# Sheet.net
KiCad netlist of a schematic drawn in Altium Designer
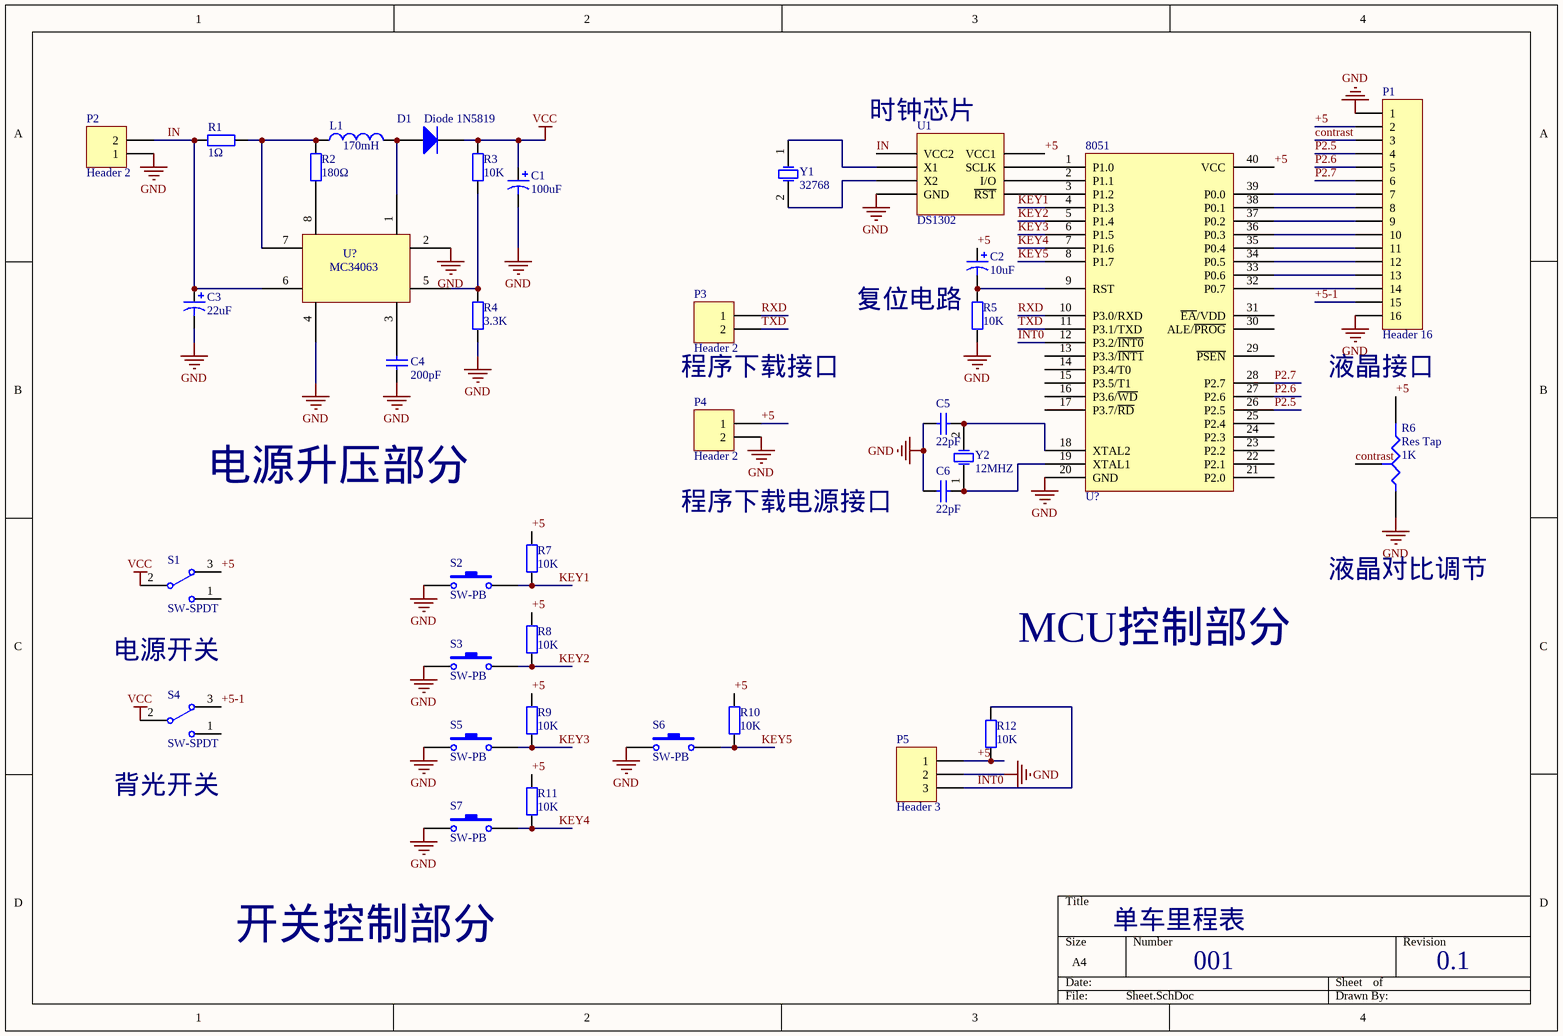
[diagram p0: Sheet.SchDoc]

(export (version "E")
  (design (tool "Eeschema 10.0.6"))
  (components
    (comp (ref "8051") (value "U?") (footprint "DIP-40") (libsource (lib "Schlib") (part "8051")))
    (comp (ref "C1")
      (value "100uF")
      (footprint "CAP-.1/.3")
      (description "Polarized Capacitor (Radial)")
      (fields (field (name "Comment") "Cap Pol1") (field (name "PUBLISHER") "Altium Limited"))
      (libsource (lib "Miscellaneous Devices") (part "Cap Pol1"))
    )
    (comp (ref "C2")
      (value "10uF")
      (footprint "CAP-.1/.2")
      (description "Polarized Capacitor (Radial)")
      (fields (field (name "Comment") "Cap Pol1") (field (name "PUBLISHER") "Altium Limited"))
      (libsource (lib "Miscellaneous Devices") (part "Cap Pol1"))
    )
    (comp (ref "C3")
      (value "22uF")
      (footprint "CAP-.1/.2")
      (description "Polarized Capacitor (Radial)")
      (fields (field (name "Comment") "Cap Pol1") (field (name "PUBLISHER") "Altium Limited"))
      (libsource (lib "Miscellaneous Devices") (part "Cap Pol1"))
    )
    (comp (ref "C4")
      (value "200pF")
      (footprint "CAP")
      (description "Capacitor")
      (fields (field (name "Comment") "Cap") (field (name "PUBLISHER") "Altium Limited"))
      (libsource (lib "Miscellaneous Devices") (part "Cap"))
    )
    (comp (ref "C5")
      (value "22pF")
      (footprint "CAP")
      (description "Capacitor")
      (fields (field (name "Comment") "Cap") (field (name "PUBLISHER") "Altium Limited"))
      (libsource (lib "Miscellaneous Devices") (part "Cap"))
    )
    (comp (ref "C6")
      (value "22pF")
      (footprint "CAP")
      (description "Capacitor")
      (fields (field (name "Comment") "Cap") (field (name "PUBLISHER") "Altium Limited"))
      (libsource (lib "Miscellaneous Devices") (part "Cap"))
    )
    (comp (ref "D1")
      (value "Diode 1N5819")
      (footprint "DO-41")
      (description "1 Amp General Purpose Rectifier")
      (fields (field (name "PUBLISHER") "Altium Limited"))
      (libsource (lib "Miscellaneous Devices") (part "Diode 1N4001"))
    )
    (comp (ref "L1")
      (value "170mH")
      (footprint "Inductor")
      (description "Inductor")
      (fields (field (name "PUBLISHER") "Altium Limited"))
      (libsource (lib "Miscellaneous Devices") (part "Inductor"))
    )
    (comp (ref "MC34063") (value "U?") (footprint "DIP-8") (libsource (lib "Schlib") (part "MC34063")))
    (comp (ref "P1")
      (value "Header 16")
      (footprint "HDR1X16")
      (description "Header, 16-Pin")
      (fields (field (name "PUBLISHER") "Altium Limited"))
      (libsource (lib "Miscellaneous Connectors") (part "Header 16"))
    )
    (comp (ref "P2")
      (value "Header 2")
      (footprint "HDR1X2")
      (description "Header, 2-Pin")
      (fields (field (name "PUBLISHER") "Altium Limited"))
      (libsource (lib "") (part "Header 2_1"))
    )
    (comp (ref "P3")
      (value "Header 2")
      (footprint "HDR1X2")
      (description "Header, 2-Pin")
      (fields (field (name "PUBLISHER") "Altium Limited"))
      (libsource (lib "Miscellaneous Connectors") (part "Header 2"))
    )
    (comp (ref "P4")
      (value "Header 2")
      (footprint "HDR1X2")
      (description "Header, 2-Pin")
      (fields (field (name "PUBLISHER") "Altium Limited"))
      (libsource (lib "Miscellaneous Connectors") (part "Header 2"))
    )
    (comp (ref "P5")
      (value "Header 3")
      (footprint "HDR1X3")
      (description "Header, 3-Pin")
      (fields (field (name "PUBLISHER") "Altium Limited"))
      (libsource (lib "Miscellaneous Connectors") (part "Header 3"))
    )
    (comp (ref "R1")
      (value "1Ω")
      (footprint "AXIAL-0.4")
      (description "Resistor")
      (fields (field (name "Comment") "Res2") (field (name "PUBLISHER") "Altium Limited"))
      (libsource (lib "") (part "Res2_1"))
    )
    (comp (ref "R2")
      (value "180Ω")
      (footprint "AXIAL-0.4")
      (description "Resistor")
      (fields (field (name "Comment") "Res2") (field (name "PUBLISHER") "Altium Limited"))
      (libsource (lib "") (part "Res2_2"))
    )
    (comp (ref "R3")
      (value "10K")
      (footprint "AXIAL-0.4")
      (description "Resistor")
      (fields (field (name "Comment") "Res2") (field (name "PUBLISHER") "Altium Limited"))
      (libsource (lib "Miscellaneous Devices") (part "Res2"))
    )
    (comp (ref "R4")
      (value "3.3K")
      (footprint "AXIAL-0.4")
      (description "Resistor")
      (fields (field (name "Comment") "Res2") (field (name "PUBLISHER") "Altium Limited"))
      (libsource (lib "Miscellaneous Devices") (part "Res2"))
    )
    (comp (ref "R5")
      (value "10K")
      (footprint "AXIAL-0.4")
      (description "Resistor")
      (fields (field (name "Comment") "Res2") (field (name "PUBLISHER") "Altium Limited"))
      (libsource (lib "Miscellaneous Devices") (part "Res2"))
    )
    (comp (ref "R6")
      (value "Res Tap")
      (footprint "RW")
      (description "Tapped Resistor")
      (fields (field (name "ALTIUM_VALUE") "1K") (field (name "PUBLISHER") "Altium Limited"))
      (libsource (lib "Miscellaneous Devices") (part "Res Tap"))
    )
    (comp (ref "R7")
      (value "10K")
      (footprint "AXIAL-0.4")
      (description "Resistor")
      (fields (field (name "Comment") "Res2") (field (name "PUBLISHER") "Altium Limited"))
      (libsource (lib "Miscellaneous Devices") (part "Res2"))
    )
    (comp (ref "R8")
      (value "10K")
      (footprint "AXIAL-0.4")
      (description "Resistor")
      (fields (field (name "Comment") "Res2") (field (name "PUBLISHER") "Altium Limited"))
      (libsource (lib "Miscellaneous Devices") (part "Res2"))
    )
    (comp (ref "R9")
      (value "10K")
      (footprint "AXIAL-0.4")
      (description "Resistor")
      (fields (field (name "Comment") "Res2") (field (name "PUBLISHER") "Altium Limited"))
      (libsource (lib "Miscellaneous Devices") (part "Res2"))
    )
    (comp (ref "R10")
      (value "10K")
      (footprint "AXIAL-0.4")
      (description "Resistor")
      (fields (field (name "Comment") "Res2") (field (name "PUBLISHER") "Altium Limited"))
      (libsource (lib "Miscellaneous Devices") (part "Res2"))
    )
    (comp (ref "R11")
      (value "10K")
      (footprint "AXIAL-0.4")
      (description "Resistor")
      (fields (field (name "Comment") "Res2") (field (name "PUBLISHER") "Altium Limited"))
      (libsource (lib "Miscellaneous Devices") (part "Res2"))
    )
    (comp (ref "R12")
      (value "10K")
      (footprint "AXIAL-0.4")
      (description "Resistor")
      (fields (field (name "Comment") "Res2") (field (name "PUBLISHER") "Altium Limited"))
      (libsource (lib "") (part "Res2_2"))
    )
    (comp (ref "S1")
      (value "SW-SPDT")
      (footprint "SW-6")
      (description "SPDT Subminiature Toggle Switch, Right Angle Mounting, Vertical Actuation")
      (fields (field (name "PUBLISHER") "Altium Limited"))
      (libsource (lib "Miscellaneous Devices") (part "SW-SPDT"))
    )
    (comp (ref "S2")
      (value "SW-PB")
      (footprint "Switch-12/12")
      (description "Switch")
      (fields (field (name "PUBLISHER") "Altium Limited"))
      (libsource (lib "Miscellaneous Devices") (part "SW-PB"))
    )
    (comp (ref "S3")
      (value "SW-PB")
      (footprint "Switch-12/12")
      (description "Switch")
      (fields (field (name "PUBLISHER") "Altium Limited"))
      (libsource (lib "Miscellaneous Devices") (part "SW-PB"))
    )
    (comp (ref "S4")
      (value "SW-SPDT")
      (footprint "SW-6")
      (description "SPDT Subminiature Toggle Switch, Right Angle Mounting, Vertical Actuation")
      (fields (field (name "PUBLISHER") "Altium Limited"))
      (libsource (lib "Miscellaneous Devices") (part "SW-SPDT"))
    )
    (comp (ref "S5")
      (value "SW-PB")
      (footprint "Switch-12/12")
      (description "Switch")
      (fields (field (name "PUBLISHER") "Altium Limited"))
      (libsource (lib "Miscellaneous Devices") (part "SW-PB"))
    )
    (comp (ref "S6")
      (value "SW-PB")
      (footprint "Switch-12/12")
      (description "Switch")
      (fields (field (name "PUBLISHER") "Altium Limited"))
      (libsource (lib "Miscellaneous Devices") (part "SW-PB"))
    )
    (comp (ref "S7")
      (value "SW-PB")
      (footprint "Switch-12/12")
      (description "Switch")
      (fields (field (name "PUBLISHER") "Altium Limited"))
      (libsource (lib "Miscellaneous Devices") (part "SW-PB"))
    )
    (comp (ref "U1") (value "DS1302") (footprint "DIP-8") (libsource (lib "MY_Schlib") (part "DS1302")))
    (comp (ref "Y1")
      (value "32768")
      (footprint "R38")
      (description "Crystal Oscillator")
      (fields (field (name "PUBLISHER") "Altium Limited"))
      (libsource (lib "Miscellaneous Devices") (part "XTAL"))
    )
    (comp (ref "Y2")
      (value "12MHZ")
      (footprint "XTAL")
      (description "Crystal Oscillator")
      (fields (field (name "PUBLISHER") "Altium Limited"))
      (libsource (lib "Miscellaneous Devices") (part "XTAL"))
    )
  )
  (nets
    (net (code "1") (name "/+5") (class "Default")
      (node (ref "8051") (pin "40") (pinfunction "VCC_40") (pintype "passive"))
      (node (ref "C2") (pin "1") (pinfunction "1_1") (pintype "passive"))
      (node (ref "P1") (pin "2") (pinfunction "2_2") (pintype "passive"))
      (node (ref "P4") (pin "1") (pinfunction "1_1") (pintype "passive"))
      (node (ref "P5") (pin "1") (pinfunction "1_1") (pintype "passive"))
      (node (ref "R10") (pin "2") (pinfunction "2_2") (pintype "passive"))
      (node (ref "R11") (pin "2") (pinfunction "2_2") (pintype "passive"))
      (node (ref "R12") (pin "2") (pinfunction "2_2") (pintype "passive"))
      (node (ref "R6") (pin "2") (pinfunction "B_2") (pintype "passive"))
      (node (ref "R7") (pin "2") (pinfunction "2_2") (pintype "passive"))
      (node (ref "R8") (pin "2") (pinfunction "2_2") (pintype "passive"))
      (node (ref "R9") (pin "2") (pinfunction "2_2") (pintype "passive"))
      (node (ref "S1") (pin "3") (pinfunction "3_3") (pintype "passive"))
      (node (ref "U1") (pin "8") (pinfunction "VCC1_8") (pintype "passive"))
    )
    (net (code "2") (name "/+5-1") (class "Default")
      (node (ref "P1") (pin "15") (pinfunction "15_15") (pintype "passive"))
      (node (ref "S4") (pin "3") (pinfunction "3_3") (pintype "passive"))
    )
    (net (code "3") (name "/IN") (class "Default")
      (node (ref "C3") (pin "1") (pinfunction "1_1") (pintype "passive"))
      (node (ref "MC34063") (pin "6") (pinfunction "VCC_6") (pintype "passive"))
      (node (ref "P2") (pin "2") (pinfunction "2_2") (pintype "passive"))
      (node (ref "R1") (pin "1") (pinfunction "1_1") (pintype "passive"))
      (node (ref "U1") (pin "1") (pinfunction "VCC2_1") (pintype "passive"))
    )
    (net (code "4") (name "/INT0") (class "Default")
      (node (ref "8051") (pin "12") (pinfunction "P3.2/~{INT0}_12") (pintype "passive"))
      (node (ref "P5") (pin "3") (pinfunction "3_3") (pintype "passive"))
      (node (ref "R12") (pin "1") (pinfunction "1_1") (pintype "passive"))
    )
    (net (code "5") (name "/KEY1") (class "Default")
      (node (ref "8051") (pin "4") (pinfunction "P1.3_4") (pintype "passive"))
      (node (ref "R7") (pin "1") (pinfunction "1_1") (pintype "passive"))
      (node (ref "S2") (pin "2") (pinfunction "2_2") (pintype "passive"))
    )
    (net (code "6") (name "/KEY2") (class "Default")
      (node (ref "8051") (pin "5") (pinfunction "P1.4_5") (pintype "passive"))
      (node (ref "R8") (pin "1") (pinfunction "1_1") (pintype "passive"))
      (node (ref "S3") (pin "2") (pinfunction "2_2") (pintype "passive"))
    )
    (net (code "7") (name "/KEY3") (class "Default")
      (node (ref "8051") (pin "6") (pinfunction "P1.5_6") (pintype "passive"))
      (node (ref "R9") (pin "1") (pinfunction "1_1") (pintype "passive"))
      (node (ref "S5") (pin "2") (pinfunction "2_2") (pintype "passive"))
    )
    (net (code "8") (name "/KEY4") (class "Default")
      (node (ref "8051") (pin "7") (pinfunction "P1.6_7") (pintype "passive"))
      (node (ref "R11") (pin "1") (pinfunction "1_1") (pintype "passive"))
      (node (ref "S7") (pin "2") (pinfunction "2_2") (pintype "passive"))
    )
    (net (code "9") (name "/KEY5") (class "Default")
      (node (ref "8051") (pin "8") (pinfunction "P1.7_8") (pintype "passive"))
      (node (ref "R10") (pin "1") (pinfunction "1_1") (pintype "passive"))
      (node (ref "S6") (pin "2") (pinfunction "2_2") (pintype "passive"))
    )
    (net (code "10") (name "/P2.5") (class "Default")
      (node (ref "8051") (pin "26") (pinfunction "P2.5_26") (pintype "passive"))
      (node (ref "P1") (pin "4") (pinfunction "4_4") (pintype "passive"))
    )
    (net (code "11") (name "/P2.6") (class "Default")
      (node (ref "8051") (pin "27") (pinfunction "P2.6_27") (pintype "passive"))
      (node (ref "P1") (pin "5") (pinfunction "5_5") (pintype "passive"))
    )
    (net (code "12") (name "/P2.7") (class "Default")
      (node (ref "8051") (pin "28") (pinfunction "P2.7_28") (pintype "passive"))
      (node (ref "P1") (pin "6") (pinfunction "6_6") (pintype "passive"))
    )
    (net (code "13") (name "/RXD") (class "Default")
      (node (ref "8051") (pin "10") (pinfunction "P3.0/RXD_10") (pintype "passive"))
      (node (ref "P3") (pin "1") (pinfunction "1_1") (pintype "passive"))
    )
    (net (code "14") (name "/TXD") (class "Default")
      (node (ref "8051") (pin "11") (pinfunction "P3.1/TXD_11") (pintype "passive"))
      (node (ref "P3") (pin "2") (pinfunction "2_2") (pintype "passive"))
    )
    (net (code "15") (name "/contrast") (class "Default")
      (node (ref "P1") (pin "3") (pinfunction "3_3") (pintype "passive"))
      (node (ref "R6") (pin "3") (pinfunction "TAP_3") (pintype "passive"))
    )
    (net (code "16") (name "GND") (class "Default")
      (node (ref "8051") (pin "20") (pinfunction "GND_20") (pintype "passive"))
      (node (ref "C1") (pin "2") (pinfunction "2_2") (pintype "passive"))
      (node (ref "C3") (pin "2") (pinfunction "2_2") (pintype "passive"))
      (node (ref "C4") (pin "1") (pinfunction "1_1") (pintype "passive"))
      (node (ref "C5") (pin "2") (pinfunction "2_2") (pintype "passive"))
      (node (ref "C6") (pin "2") (pinfunction "2_2") (pintype "passive"))
      (node (ref "MC34063") (pin "2") (pinfunction "Switch_Emitter_2") (pintype "passive"))
      (node (ref "MC34063") (pin "4") (pinfunction "GND_4") (pintype "passive"))
      (node (ref "P1") (pin "1") (pinfunction "1_1") (pintype "passive"))
      (node (ref "P1") (pin "16") (pinfunction "16_16") (pintype "passive"))
      (node (ref "P2") (pin "1") (pinfunction "1_1") (pintype "passive"))
      (node (ref "P4") (pin "2") (pinfunction "2_2") (pintype "passive"))
      (node (ref "P5") (pin "2") (pinfunction "2_2") (pintype "passive"))
      (node (ref "R4") (pin "1") (pinfunction "1_1") (pintype "passive"))
      (node (ref "R5") (pin "1") (pinfunction "1_1") (pintype "passive"))
      (node (ref "R6") (pin "1") (pinfunction "A_1") (pintype "passive"))
      (node (ref "S2") (pin "1") (pinfunction "1_1") (pintype "passive"))
      (node (ref "S3") (pin "1") (pinfunction "1_1") (pintype "passive"))
      (node (ref "S5") (pin "1") (pinfunction "1_1") (pintype "passive"))
      (node (ref "S6") (pin "1") (pinfunction "1_1") (pintype "passive"))
      (node (ref "S7") (pin "1") (pinfunction "1_1") (pintype "passive"))
      (node (ref "U1") (pin "4") (pinfunction "GND_4") (pintype "passive"))
    )
    (net (code "17") (name "Net-(8051-P0.0)") (class "Default")
      (node (ref "8051") (pin "39") (pinfunction "P0.0_39") (pintype "passive"))
      (node (ref "P1") (pin "7") (pinfunction "7_7") (pintype "passive"))
    )
    (net (code "18") (name "Net-(8051-P0.1)") (class "Default")
      (node (ref "8051") (pin "38") (pinfunction "P0.1_38") (pintype "passive"))
      (node (ref "P1") (pin "8") (pinfunction "8_8") (pintype "passive"))
    )
    (net (code "19") (name "Net-(8051-P0.2)") (class "Default")
      (node (ref "8051") (pin "37") (pinfunction "P0.2_37") (pintype "passive"))
      (node (ref "P1") (pin "9") (pinfunction "9_9") (pintype "passive"))
    )
    (net (code "20") (name "Net-(8051-P0.3)") (class "Default")
      (node (ref "8051") (pin "36") (pinfunction "P0.3_36") (pintype "passive"))
      (node (ref "P1") (pin "10") (pinfunction "10_10") (pintype "passive"))
    )
    (net (code "21") (name "Net-(8051-P0.4)") (class "Default")
      (node (ref "8051") (pin "35") (pinfunction "P0.4_35") (pintype "passive"))
      (node (ref "P1") (pin "11") (pinfunction "11_11") (pintype "passive"))
    )
    (net (code "22") (name "Net-(8051-P0.5)") (class "Default")
      (node (ref "8051") (pin "34") (pinfunction "P0.5_34") (pintype "passive"))
      (node (ref "P1") (pin "12") (pinfunction "12_12") (pintype "passive"))
    )
    (net (code "23") (name "Net-(8051-P0.6)") (class "Default")
      (node (ref "8051") (pin "33") (pinfunction "P0.6_33") (pintype "passive"))
      (node (ref "P1") (pin "13") (pinfunction "13_13") (pintype "passive"))
    )
    (net (code "24") (name "Net-(8051-P0.7)") (class "Default")
      (node (ref "8051") (pin "32") (pinfunction "P0.7_32") (pintype "passive"))
      (node (ref "P1") (pin "14") (pinfunction "14_14") (pintype "passive"))
    )
    (net (code "25") (name "Net-(8051-P1.0)") (class "Default")
      (node (ref "8051") (pin "1") (pinfunction "P1.0_1") (pintype "passive"))
      (node (ref "U1") (pin "7") (pinfunction "SCLK_7") (pintype "passive"))
    )
    (net (code "26") (name "Net-(8051-P1.1)") (class "Default")
      (node (ref "8051") (pin "2") (pinfunction "P1.1_2") (pintype "passive"))
      (node (ref "U1") (pin "6") (pinfunction "I/O_6") (pintype "passive"))
    )
    (net (code "27") (name "Net-(8051-P1.2)") (class "Default")
      (node (ref "8051") (pin "3") (pinfunction "P1.2_3") (pintype "passive"))
      (node (ref "U1") (pin "5") (pinfunction "~{RST}_5") (pintype "passive"))
    )
    (net (code "28") (name "Net-(8051-RST)") (class "Default")
      (node (ref "8051") (pin "9") (pinfunction "RST_9") (pintype "passive"))
      (node (ref "C2") (pin "2") (pinfunction "2_2") (pintype "passive"))
      (node (ref "R5") (pin "2") (pinfunction "2_2") (pintype "passive"))
    )
    (net (code "29") (name "Net-(8051-XTAL1)") (class "Default")
      (node (ref "8051") (pin "19") (pinfunction "XTAL1_19") (pintype "passive"))
      (node (ref "C6") (pin "1") (pinfunction "1_1") (pintype "passive"))
      (node (ref "Y2") (pin "1") (pinfunction "OSC1_1") (pintype "passive"))
    )
    (net (code "30") (name "Net-(8051-XTAL2)") (class "Default")
      (node (ref "8051") (pin "18") (pinfunction "XTAL2_18") (pintype "passive"))
      (node (ref "C5") (pin "1") (pinfunction "1_1") (pintype "passive"))
      (node (ref "Y2") (pin "2") (pinfunction "OSC2_2") (pintype "passive"))
    )
    (net (code "31") (name "Net-(D1-A)") (class "Default")
      (node (ref "D1") (pin "1") (pinfunction "A_1") (pintype "passive"))
      (node (ref "L1") (pin "2") (pinfunction "2_2") (pintype "passive"))
      (node (ref "MC34063") (pin "1") (pinfunction "Switch_Collector_1") (pintype "passive"))
    )
    (net (code "32") (name "Net-(MC34063-Comparator_Inverting_Input)") (class "Default")
      (node (ref "MC34063") (pin "5") (pinfunction "Comparator_Inverting_Input_5") (pintype "passive"))
      (node (ref "R3") (pin "1") (pinfunction "1_1") (pintype "passive"))
      (node (ref "R4") (pin "2") (pinfunction "2_2") (pintype "passive"))
    )
    (net (code "33") (name "Net-(MC34063-Driver_Collector)") (class "Default")
      (node (ref "MC34063") (pin "8") (pinfunction "Driver_Collector_8") (pintype "passive"))
      (node (ref "R2") (pin "2") (pinfunction "2_2") (pintype "passive"))
    )
    (net (code "34") (name "Net-(MC34063-Ipk)") (class "Default")
      (node (ref "L1") (pin "1") (pinfunction "1_1") (pintype "passive"))
      (node (ref "MC34063") (pin "7") (pinfunction "Ipk_7") (pintype "passive"))
      (node (ref "R1") (pin "2") (pinfunction "2_2") (pintype "passive"))
      (node (ref "R2") (pin "1") (pinfunction "1_1") (pintype "passive"))
    )
    (net (code "35") (name "Net-(MC34063-Timing_Capacitor)") (class "Default")
      (node (ref "C4") (pin "2") (pinfunction "2_2") (pintype "passive"))
      (node (ref "MC34063") (pin "3") (pinfunction "Timing_Capacitor_3") (pintype "passive"))
    )
    (net (code "36") (name "Net-(U1-X1)") (class "Default")
      (node (ref "U1") (pin "2") (pinfunction "X1_2") (pintype "passive"))
      (node (ref "Y1") (pin "1") (pinfunction "OSC1_1") (pintype "passive"))
    )
    (net (code "37") (name "Net-(U1-X2)") (class "Default")
      (node (ref "U1") (pin "3") (pinfunction "X2_3") (pintype "passive"))
      (node (ref "Y1") (pin "2") (pinfunction "OSC2_2") (pintype "passive"))
    )
    (net (code "38") (name "VCC") (class "Default")
      (node (ref "C1") (pin "1") (pinfunction "1_1") (pintype "passive"))
      (node (ref "D1") (pin "2") (pinfunction "K_2") (pintype "passive"))
      (node (ref "R3") (pin "2") (pinfunction "2_2") (pintype "passive"))
      (node (ref "S1") (pin "2") (pinfunction "2_2") (pintype "passive"))
      (node (ref "S4") (pin "2") (pinfunction "2_2") (pintype "passive"))
    )
    (net (code "39") (name "unconnected-(8051-ALE{slash}~{PROG}-Pad30)") (class "Default")
      (node (ref "8051") (pin "30") (pinfunction "ALE/~{PROG}_30") (pintype "passive"))
    )
    (net (code "40") (name "unconnected-(8051-P2.0-Pad21)") (class "Default")
      (node (ref "8051") (pin "21") (pinfunction "P2.0_21") (pintype "passive"))
    )
    (net (code "41") (name "unconnected-(8051-P2.1-Pad22)") (class "Default")
      (node (ref "8051") (pin "22") (pinfunction "P2.1_22") (pintype "passive"))
    )
    (net (code "42") (name "unconnected-(8051-P2.2-Pad23)") (class "Default")
      (node (ref "8051") (pin "23") (pinfunction "P2.2_23") (pintype "passive"))
    )
    (net (code "43") (name "unconnected-(8051-P2.3-Pad24)") (class "Default")
      (node (ref "8051") (pin "24") (pinfunction "P2.3_24") (pintype "passive"))
    )
    (net (code "44") (name "unconnected-(8051-P2.4-Pad25)") (class "Default")
      (node (ref "8051") (pin "25") (pinfunction "P2.4_25") (pintype "passive"))
    )
    (net (code "45") (name "unconnected-(8051-P3.3{slash}~{INT1}-Pad13)") (class "Default")
      (node (ref "8051") (pin "13") (pinfunction "P3.3/~{INT1}_13") (pintype "passive"))
    )
    (net (code "46") (name "unconnected-(8051-P3.4{slash}T0-Pad14)") (class "Default")
      (node (ref "8051") (pin "14") (pinfunction "P3.4/T0_14") (pintype "passive"))
    )
    (net (code "47") (name "unconnected-(8051-P3.5{slash}T1-Pad15)") (class "Default")
      (node (ref "8051") (pin "15") (pinfunction "P3.5/T1_15") (pintype "passive"))
    )
    (net (code "48") (name "unconnected-(8051-P3.6{slash}~{WD}-Pad16)") (class "Default")
      (node (ref "8051") (pin "16") (pinfunction "P3.6/~{WD}_16") (pintype "passive"))
    )
    (net (code "49") (name "unconnected-(8051-P3.7{slash}~{RD}-Pad17)") (class "Default")
      (node (ref "8051") (pin "17") (pinfunction "P3.7/~{RD}_17") (pintype "passive"))
    )
    (net (code "50") (name "unconnected-(8051-~{EA}{slash}VDD-Pad31)") (class "Default")
      (node (ref "8051") (pin "31") (pinfunction "~{EA}/VDD_31") (pintype "passive"))
    )
    (net (code "51") (name "unconnected-(8051-~{PSEN}-Pad29)") (class "Default")
      (node (ref "8051") (pin "29") (pinfunction "~{PSEN}_29") (pintype "passive"))
    )
    (net (code "52") (name "unconnected-(S1-Pad1)") (class "Default")
      (node (ref "S1") (pin "1") (pinfunction "1_1") (pintype "passive"))
    )
    (net (code "53") (name "unconnected-(S4-Pad1)") (class "Default")
      (node (ref "S4") (pin "1") (pinfunction "1_1") (pintype "passive"))
    )
  )
)
